# reLoaD_Spinner.net
KiCad netlist of a schematic drawn in EAGLE
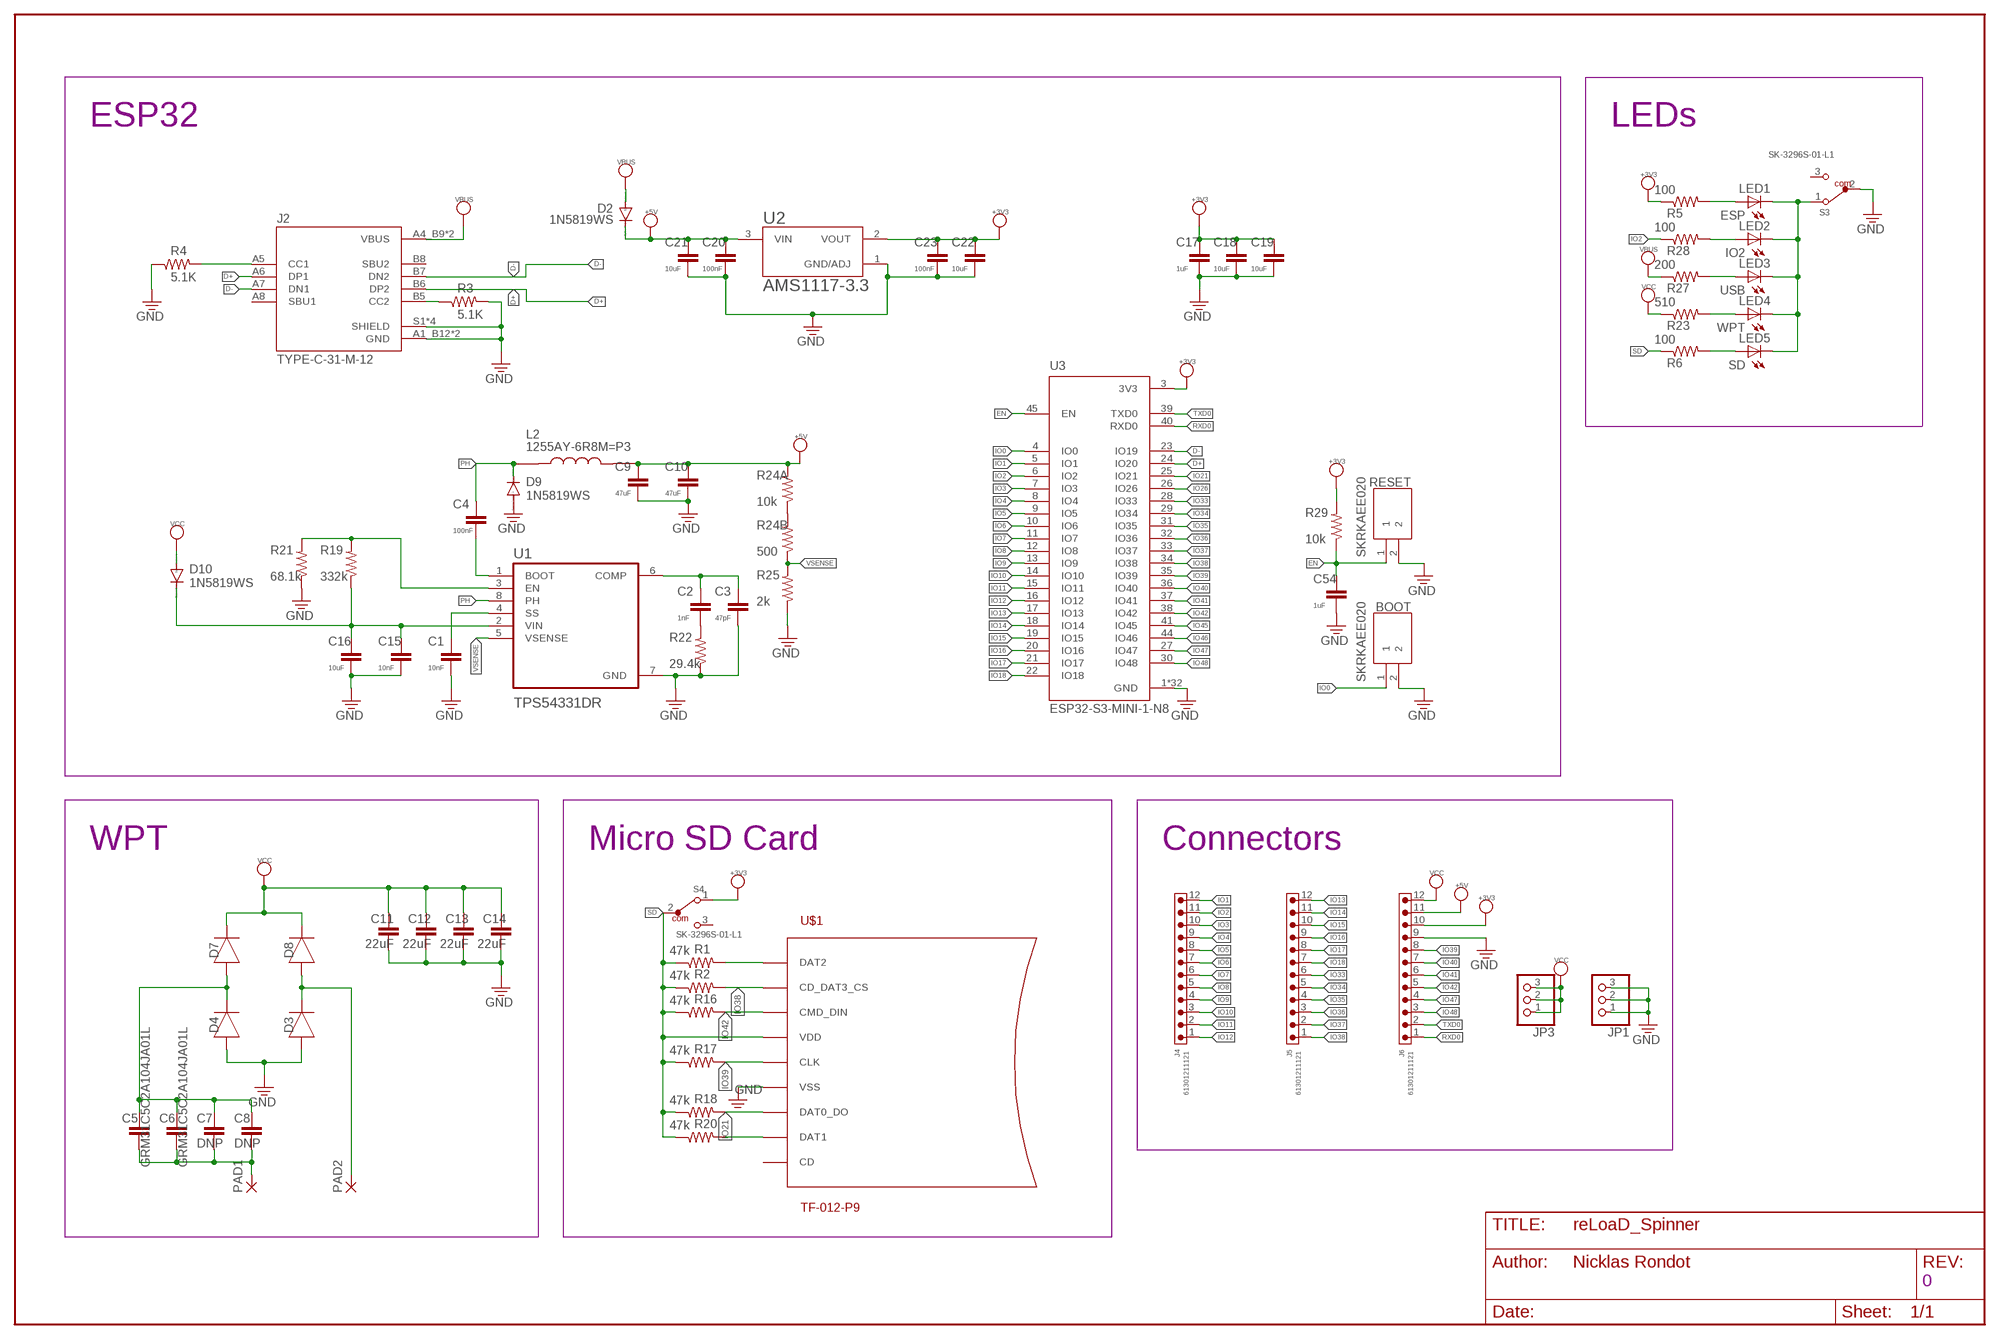
[diagram p0: schematic, sheet 1]

(export (version "E")
  (design (tool "Eeschema 10.0.6"))
  (components
    (comp (ref "BOOT")
      (value "SKRKAEE020")
      (footprint "eagle-import:SKRKAEE020")
      (fields (field (name "MOUSER_PART_NUMBER") "688-SKRKAEE020"))
      (libsource (lib "eagle-import") (part "SKRKAEE020"))
    )
    (comp (ref "C1")
      (value "10nF")
      (footprint "eagle-import:C0603K")
      (libsource (lib "eagle-import") (part "resistor_348_C-EUC0603K"))
    )
    (comp (ref "C2")
      (value "1nF")
      (footprint "eagle-import:C0603K")
      (libsource (lib "eagle-import") (part "resistor_348_C-EUC0603K"))
    )
    (comp (ref "C3")
      (value "47pF")
      (footprint "eagle-import:C0603K")
      (libsource (lib "eagle-import") (part "resistor_348_C-EUC0603K"))
    )
    (comp (ref "C4")
      (value "100nF")
      (footprint "eagle-import:C0603K")
      (libsource (lib "eagle-import") (part "resistor_348_C-EUC0603K"))
    )
    (comp (ref "C5")
      (value "GRM31C5C2A104JA01L")
      (footprint "eagle-import:C1206K")
      (libsource (lib "eagle-import") (part "C-EUC1206K"))
    )
    (comp (ref "C6")
      (value "GRM31C5C2A104JA01L")
      (footprint "eagle-import:C1206K")
      (libsource (lib "eagle-import") (part "C-EUC1206K"))
    )
    (comp (ref "C7")
      (value "DNP")
      (footprint "eagle-import:C1206K")
      (libsource (lib "eagle-import") (part "C-EUC1206K"))
    )
    (comp (ref "C8")
      (value "DNP")
      (footprint "eagle-import:C1206K")
      (libsource (lib "eagle-import") (part "C-EUC1206K"))
    )
    (comp (ref "C9")
      (value "47uF")
      (footprint "eagle-import:C0603K")
      (libsource (lib "eagle-import") (part "resistor_348_C-EUC0603K"))
    )
    (comp (ref "C10")
      (value "47uF")
      (footprint "eagle-import:C0603K")
      (libsource (lib "eagle-import") (part "resistor_348_C-EUC0603K"))
    )
    (comp (ref "C11")
      (value "22uF")
      (footprint "eagle-import:C0805K")
      (libsource (lib "eagle-import") (part "C-EUC0805K"))
    )
    (comp (ref "C12")
      (value "22uF")
      (footprint "eagle-import:C0805K")
      (libsource (lib "eagle-import") (part "C-EUC0805K"))
    )
    (comp (ref "C13")
      (value "22uF")
      (footprint "eagle-import:C0805K")
      (libsource (lib "eagle-import") (part "C-EUC0805K"))
    )
    (comp (ref "C14")
      (value "22uF")
      (footprint "eagle-import:C0805K")
      (libsource (lib "eagle-import") (part "C-EUC0805K"))
    )
    (comp (ref "C15")
      (value "10nF")
      (footprint "eagle-import:C0603K")
      (libsource (lib "eagle-import") (part "resistor_348_C-EUC0603K"))
    )
    (comp (ref "C16")
      (value "10uF")
      (footprint "eagle-import:C0603K")
      (libsource (lib "eagle-import") (part "resistor_348_C-EUC0603K"))
    )
    (comp (ref "C17")
      (value "1uF")
      (footprint "eagle-import:C0603K")
      (libsource (lib "eagle-import") (part "resistor_348_C-EUC0603K"))
    )
    (comp (ref "C18")
      (value "10uF")
      (footprint "eagle-import:C0603K")
      (libsource (lib "eagle-import") (part "resistor_348_C-EUC0603K"))
    )
    (comp (ref "C19")
      (value "10uF")
      (footprint "eagle-import:C0603K")
      (libsource (lib "eagle-import") (part "resistor_348_C-EUC0603K"))
    )
    (comp (ref "C20")
      (value "100nF")
      (footprint "eagle-import:C0603K")
      (libsource (lib "eagle-import") (part "resistor_348_C-EUC0603K"))
    )
    (comp (ref "C21")
      (value "10uF")
      (footprint "eagle-import:C0603K")
      (libsource (lib "eagle-import") (part "resistor_348_C-EUC0603K"))
    )
    (comp (ref "C22")
      (value "10uF")
      (footprint "eagle-import:C0603K")
      (libsource (lib "eagle-import") (part "resistor_348_C-EUC0603K"))
    )
    (comp (ref "C23")
      (value "100nF")
      (footprint "eagle-import:C0603K")
      (libsource (lib "eagle-import") (part "resistor_348_C-EUC0603K"))
    )
    (comp (ref "C54")
      (value "1uF")
      (footprint "eagle-import:C0603K")
      (libsource (lib "eagle-import") (part "resistor_348_C-EUC0603K"))
    )
    (comp (ref "D2")
      (value "1N5819WS")
      (footprint "eagle-import:SOD323-W")
      (libsource (lib "eagle-import") (part "DIODE-SOD323-W"))
    )
    (comp (ref "D3")
      (value "DIODE")
      (footprint "eagle-import:DIOM5226X290N")
      (libsource (lib "eagle-import") (part "DIODEDO-214AC(SMA)"))
    )
    (comp (ref "D4")
      (value "DIODE")
      (footprint "eagle-import:DIOM5226X290N")
      (libsource (lib "eagle-import") (part "DIODEDO-214AC(SMA)"))
    )
    (comp (ref "D7")
      (value "DIODE")
      (footprint "eagle-import:DIOM5226X290N")
      (libsource (lib "eagle-import") (part "DIODEDO-214AC(SMA)"))
    )
    (comp (ref "D8")
      (value "DIODE")
      (footprint "eagle-import:DIOM5226X290N")
      (libsource (lib "eagle-import") (part "DIODEDO-214AC(SMA)"))
    )
    (comp (ref "D9")
      (value "1N5819WS")
      (footprint "eagle-import:SOD323-W")
      (libsource (lib "eagle-import") (part "DIODE-SOD323-W"))
    )
    (comp (ref "D10")
      (value "1N5819WS")
      (footprint "eagle-import:SOD323-W")
      (libsource (lib "eagle-import") (part "DIODE-SOD323-W"))
    )
    (comp (ref "J2")
      (value "TYPE-C-31-M-12")
      (footprint "eagle-import:HRO_TYPE-C-31-M-12")
      (fields (field (name "MF") "HRO Electronics Co., Ltd."))
      (libsource (lib "eagle-import") (part "TYPE-C-31-M-12"))
    )
    (comp (ref "J4")
      (value "61301211121")
      (footprint "eagle-import:61301211121")
      (libsource (lib "eagle-import") (part "6130XX11121_61301211121"))
    )
    (comp (ref "J5")
      (value "61301211121")
      (footprint "eagle-import:61301211121")
      (libsource (lib "eagle-import") (part "6130XX11121_61301211121"))
    )
    (comp (ref "J6")
      (value "61301211121")
      (footprint "eagle-import:61301211121")
      (libsource (lib "eagle-import") (part "6130XX11121_61301211121"))
    )
    (comp (ref "JP1")
      (value "PINHD-1X3")
      (footprint "eagle-import:1X03")
      (libsource (lib "eagle-import") (part "PINHD-1X3"))
    )
    (comp (ref "JP3")
      (value "PINHD-1X3")
      (footprint "eagle-import:1X03")
      (libsource (lib "eagle-import") (part "PINHD-1X3"))
    )
    (comp (ref "L2")
      (value "1255AY-6R8M=P3")
      (footprint "eagle-import:IND_1255AY-6R8M=P3")
      (fields (field (name "MF") "Murata Electronics"))
      (libsource (lib "eagle-import") (part "1255AY-6R8M=P3"))
    )
    (comp (ref "LED1")
      (value "ESP")
      (footprint "eagle-import:CHIPLED_0805")
      (libsource (lib "eagle-import") (part "LEDCHIPLED_0805"))
    )
    (comp (ref "LED2")
      (value "IO2")
      (footprint "eagle-import:CHIPLED_0805")
      (libsource (lib "eagle-import") (part "LEDCHIPLED_0805"))
    )
    (comp (ref "LED3")
      (value "USB")
      (footprint "eagle-import:CHIPLED_0805")
      (libsource (lib "eagle-import") (part "LEDCHIPLED_0805"))
    )
    (comp (ref "LED4")
      (value "WPT")
      (footprint "eagle-import:CHIPLED_0805")
      (libsource (lib "eagle-import") (part "LEDCHIPLED_0805"))
    )
    (comp (ref "LED5")
      (value "SD")
      (footprint "eagle-import:CHIPLED_0805")
      (libsource (lib "eagle-import") (part "LEDCHIPLED_0805"))
    )
    (comp (ref "PAD1")
      (value "3,81/1,4")
      (footprint "eagle-import:3,81_1,4")
      (libsource (lib "eagle-import") (part "3,81/1,4"))
    )
    (comp (ref "PAD2")
      (value "3,81/1,4")
      (footprint "eagle-import:3,81_1,4")
      (libsource (lib "eagle-import") (part "3,81/1,4"))
    )
    (comp (ref "R1")
      (value "47k")
      (footprint "eagle-import:R0603")
      (libsource (lib "eagle-import") (part "R-US_R0603"))
    )
    (comp (ref "R2")
      (value "47k")
      (footprint "eagle-import:R0603")
      (libsource (lib "eagle-import") (part "R-US_R0603"))
    )
    (comp (ref "R3")
      (value "5.1K")
      (footprint "eagle-import:R0603")
      (libsource (lib "eagle-import") (part "R-US_R0603"))
    )
    (comp (ref "R4")
      (value "5.1K")
      (footprint "eagle-import:R0603")
      (libsource (lib "eagle-import") (part "R-US_R0603"))
    )
    (comp (ref "R5")
      (value "100")
      (footprint "eagle-import:R0603")
      (libsource (lib "eagle-import") (part "R-US_R0603"))
    )
    (comp (ref "R6")
      (value "100")
      (footprint "eagle-import:R0603")
      (libsource (lib "eagle-import") (part "R-US_R0603"))
    )
    (comp (ref "R16")
      (value "47k")
      (footprint "eagle-import:R0603")
      (libsource (lib "eagle-import") (part "R-US_R0603"))
    )
    (comp (ref "R17")
      (value "47k")
      (footprint "eagle-import:R0603")
      (libsource (lib "eagle-import") (part "R-US_R0603"))
    )
    (comp (ref "R18")
      (value "47k")
      (footprint "eagle-import:R0603")
      (libsource (lib "eagle-import") (part "R-US_R0603"))
    )
    (comp (ref "R19")
      (value "332k")
      (footprint "eagle-import:R0603")
      (libsource (lib "eagle-import") (part "R-US_R0603"))
    )
    (comp (ref "R20")
      (value "47k")
      (footprint "eagle-import:R0603")
      (libsource (lib "eagle-import") (part "R-US_R0603"))
    )
    (comp (ref "R21")
      (value "68.1k")
      (footprint "eagle-import:R0603")
      (libsource (lib "eagle-import") (part "R-US_R0603"))
    )
    (comp (ref "R22")
      (value "29.4k")
      (footprint "eagle-import:R0603")
      (libsource (lib "eagle-import") (part "R-US_R0603"))
    )
    (comp (ref "R23")
      (value "510")
      (footprint "eagle-import:R0603")
      (libsource (lib "eagle-import") (part "R-US_R0603"))
    )
    (comp (ref "R24A")
      (value "10k")
      (footprint "eagle-import:R0603")
      (libsource (lib "eagle-import") (part "R-US_R0603"))
    )
    (comp (ref "R24B")
      (value "500")
      (footprint "eagle-import:R0603")
      (libsource (lib "eagle-import") (part "R-US_R0603"))
    )
    (comp (ref "R25")
      (value "2k")
      (footprint "eagle-import:R0603")
      (libsource (lib "eagle-import") (part "R-US_R0603"))
    )
    (comp (ref "R27")
      (value "200")
      (footprint "eagle-import:R0603")
      (libsource (lib "eagle-import") (part "R-US_R0603"))
    )
    (comp (ref "R28")
      (value "100")
      (footprint "eagle-import:R0603")
      (libsource (lib "eagle-import") (part "R-US_R0603"))
    )
    (comp (ref "R29")
      (value "10k")
      (footprint "eagle-import:R0603")
      (libsource (lib "eagle-import") (part "R-US_R0603"))
    )
    (comp (ref "RESET")
      (value "SKRKAEE020")
      (footprint "eagle-import:SKRKAEE020")
      (fields (field (name "MOUSER_PART_NUMBER") "688-SKRKAEE020"))
      (libsource (lib "eagle-import") (part "SKRKAEE020"))
    )
    (comp (ref "S3")
      (value "SK-3296S-01-L1")
      (footprint "eagle-import:450404015514")
      (libsource (lib "eagle-import") (part "450404015514"))
    )
    (comp (ref "S4")
      (value "SK-3296S-01-L1")
      (footprint "eagle-import:450404015514")
      (libsource (lib "eagle-import") (part "450404015514"))
    )
    (comp (ref "U$1")
      (value "TF-012-P9")
      (footprint "eagle-import:MICROSD-PUSH-OUT")
      (libsource (lib "eagle-import") (part "TF-012-P9"))
    )
    (comp (ref "U1")
      (value "TPS54331DR")
      (footprint "eagle-import:SOIC127P599X175-8N")
      (fields (field (name "MF") "Texas Instruments"))
      (libsource (lib "eagle-import") (part "TPS54331DR"))
    )
    (comp (ref "U2")
      (value "AMS1117-3.3")
      (footprint "eagle-import:SOT229P700X180-4N")
      (fields (field (name "MF") "Advanced Monolithic Systems"))
      (libsource (lib "eagle-import") (part "AMS1117-3.3"))
    )
    (comp (ref "U3")
      (value "ESP32-S3-MINI-1-N8")
      (footprint "eagle-import:XCVR_ESP32-S3-MINI-1-N8")
      (fields (field (name "MF") "Espressif Systems"))
      (libsource (lib "eagle-import") (part "ESP32-S3-MINI-1-N8"))
    )
  )
  (nets
    (net (code "1") (name "+3V3") (class "Default")
      (node (ref "C17") (pin "1") (pinfunction "1_1") (pintype "passive"))
      (node (ref "C18") (pin "1") (pinfunction "1_1") (pintype "passive"))
      (node (ref "C19") (pin "1") (pinfunction "1_1") (pintype "passive"))
      (node (ref "C22") (pin "1") (pinfunction "1_1") (pintype "passive"))
      (node (ref "C23") (pin "1") (pinfunction "1_1") (pintype "passive"))
      (node (ref "J6") (pin "10") (pinfunction "10_10") (pintype "passive"))
      (node (ref "R29") (pin "2") (pinfunction "2_2") (pintype "passive"))
      (node (ref "R5") (pin "1") (pinfunction "1_1") (pintype "passive"))
      (node (ref "S4") (pin "1") (pinfunction "1_1") (pintype "passive"))
      (node (ref "U2") (pin "2") (pinfunction "VOUT_2") (pintype "output"))
      (node (ref "U3") (pin "3") (pinfunction "3V3_3") (pintype "power_in"))
    )
    (net (code "2") (name "+5V") (class "Default")
      (node (ref "C10") (pin "1") (pinfunction "1_1") (pintype "passive"))
      (node (ref "C20") (pin "1") (pinfunction "1_1") (pintype "passive"))
      (node (ref "C21") (pin "1") (pinfunction "1_1") (pintype "passive"))
      (node (ref "C9") (pin "1") (pinfunction "1_1") (pintype "passive"))
      (node (ref "D2") (pin "C") (pinfunction "C_C") (pintype "passive"))
      (node (ref "J6") (pin "11") (pinfunction "11_11") (pintype "passive"))
      (node (ref "L2") (pin "2") (pinfunction "2_2") (pintype "passive"))
      (node (ref "R24A") (pin "2") (pinfunction "2_2") (pintype "passive"))
      (node (ref "U2") (pin "3") (pinfunction "VIN_3") (pintype "input"))
    )
    (net (code "3") (name "D+") (class "Default")
      (node (ref "J2") (pin "A6") (pinfunction "DP1_A6") (pintype "bidirectional"))
      (node (ref "J2") (pin "B6") (pinfunction "DP2_B6") (pintype "bidirectional"))
      (node (ref "U3") (pin "24") (pinfunction "IO20_24") (pintype "bidirectional"))
    )
    (net (code "4") (name "D-") (class "Default")
      (node (ref "J2") (pin "A7") (pinfunction "DN1_A7") (pintype "bidirectional"))
      (node (ref "J2") (pin "B7") (pinfunction "DN2_B7") (pintype "bidirectional"))
      (node (ref "U3") (pin "23") (pinfunction "IO19_23") (pintype "bidirectional"))
    )
    (net (code "5") (name "EN") (class "Default")
      (node (ref "C54") (pin "1") (pinfunction "1_1") (pintype "passive"))
      (node (ref "R29") (pin "1") (pinfunction "1_1") (pintype "passive"))
      (node (ref "RESET") (pin "1") (pinfunction "1_1") (pintype "bidirectional"))
      (node (ref "U3") (pin "45") (pinfunction "EN_45") (pintype "input"))
    )
    (net (code "6") (name "GND") (class "Default")
      (node (ref "BOOT") (pin "2") (pinfunction "2_2") (pintype "bidirectional"))
      (node (ref "C1") (pin "2") (pinfunction "2_2") (pintype "passive"))
      (node (ref "C10") (pin "2") (pinfunction "2_2") (pintype "passive"))
      (node (ref "C11") (pin "1") (pinfunction "1_1") (pintype "passive"))
      (node (ref "C12") (pin "1") (pinfunction "1_1") (pintype "passive"))
      (node (ref "C13") (pin "1") (pinfunction "1_1") (pintype "passive"))
      (node (ref "C14") (pin "1") (pinfunction "1_1") (pintype "passive"))
      (node (ref "C15") (pin "2") (pinfunction "2_2") (pintype "passive"))
      (node (ref "C16") (pin "2") (pinfunction "2_2") (pintype "passive"))
      (node (ref "C17") (pin "2") (pinfunction "2_2") (pintype "passive"))
      (node (ref "C18") (pin "2") (pinfunction "2_2") (pintype "passive"))
      (node (ref "C19") (pin "2") (pinfunction "2_2") (pintype "passive"))
      (node (ref "C20") (pin "2") (pinfunction "2_2") (pintype "passive"))
      (node (ref "C21") (pin "2") (pinfunction "2_2") (pintype "passive"))
      (node (ref "C22") (pin "2") (pinfunction "2_2") (pintype "passive"))
      (node (ref "C23") (pin "2") (pinfunction "2_2") (pintype "passive"))
      (node (ref "C3") (pin "2") (pinfunction "2_2") (pintype "passive"))
      (node (ref "C54") (pin "2") (pinfunction "2_2") (pintype "passive"))
      (node (ref "C9") (pin "2") (pinfunction "2_2") (pintype "passive"))
      (node (ref "D3") (pin "2") (pinfunction "A_2") (pintype "passive"))
      (node (ref "D4") (pin "2") (pinfunction "A_2") (pintype "passive"))
      (node (ref "D9") (pin "A") (pinfunction "A_A") (pintype "passive"))
      (node (ref "J2") (pin "A1_B12") (pinfunction "GND_A1_B12") (pintype "power_in"))
      (node (ref "J2") (pin "B1_A12") (pinfunction "GND_B1_A12") (pintype "power_in"))
      (node (ref "J2") (pin "S1") (pinfunction "SHIELD_S1") (pintype "passive"))
      (node (ref "J2") (pin "S2") (pinfunction "SHIELD_S2") (pintype "passive"))
      (node (ref "J2") (pin "S3") (pinfunction "SHIELD_S3") (pintype "passive"))
      (node (ref "J2") (pin "S4") (pinfunction "SHIELD_S4") (pintype "passive"))
      (node (ref "J6") (pin "9") (pinfunction "9_9") (pintype "passive"))
      (node (ref "JP1") (pin "1") (pinfunction "1_1") (pintype "passive"))
      (node (ref "JP1") (pin "2") (pinfunction "2_2") (pintype "passive"))
      (node (ref "JP1") (pin "3") (pinfunction "3_3") (pintype "passive"))
      (node (ref "R21") (pin "1") (pinfunction "1_1") (pintype "passive"))
      (node (ref "R22") (pin "1") (pinfunction "1_1") (pintype "passive"))
      (node (ref "R25") (pin "1") (pinfunction "1_1") (pintype "passive"))
      (node (ref "R3") (pin "2") (pinfunction "2_2") (pintype "passive"))
      (node (ref "R4") (pin "1") (pinfunction "1_1") (pintype "passive"))
      (node (ref "RESET") (pin "2") (pinfunction "2_2") (pintype "bidirectional"))
      (node (ref "S3") (pin "2") (pinfunction "2_2") (pintype "passive"))
      (node (ref "U$1") (pin "6") (pinfunction "VSS_6") (pintype "bidirectional"))
      (node (ref "U$1") (pin "G1") (pinfunction "VSS_G1") (pintype "bidirectional"))
      (node (ref "U$1") (pin "G2") (pinfunction "VSS_G2") (pintype "bidirectional"))
      (node (ref "U$1") (pin "G3") (pinfunction "VSS_G3") (pintype "bidirectional"))
      (node (ref "U$1") (pin "G4") (pinfunction "VSS_G4") (pintype "bidirectional"))
      (node (ref "U1") (pin "7") (pinfunction "GND_7") (pintype "power_in"))
      (node (ref "U2") (pin "1") (pinfunction "GND/ADJ_1") (pintype "power_in"))
      (node (ref "U3") (pin "1") (pinfunction "GND_1") (pintype "power_in"))
      (node (ref "U3") (pin "2") (pinfunction "GND_2") (pintype "power_in"))
      (node (ref "U3") (pin "42") (pinfunction "GND_42") (pintype "power_in"))
      (node (ref "U3") (pin "43") (pinfunction "GND_43") (pintype "power_in"))
      (node (ref "U3") (pin "46") (pinfunction "GND_46") (pintype "power_in"))
      (node (ref "U3") (pin "47") (pinfunction "GND_47") (pintype "power_in"))
      (node (ref "U3") (pin "48") (pinfunction "GND_48") (pintype "power_in"))
      (node (ref "U3") (pin "49") (pinfunction "GND_49") (pintype "power_in"))
      (node (ref "U3") (pin "50") (pinfunction "GND_50") (pintype "power_in"))
      (node (ref "U3") (pin "51") (pinfunction "GND_51") (pintype "power_in"))
      (node (ref "U3") (pin "52") (pinfunction "GND_52") (pintype "power_in"))
      (node (ref "U3") (pin "53") (pinfunction "GND_53") (pintype "power_in"))
      (node (ref "U3") (pin "54") (pinfunction "GND_54") (pintype "power_in"))
      (node (ref "U3") (pin "55") (pinfunction "GND_55") (pintype "power_in"))
      (node (ref "U3") (pin "56") (pinfunction "GND_56") (pintype "power_in"))
      (node (ref "U3") (pin "57") (pinfunction "GND_57") (pintype "power_in"))
      (node (ref "U3") (pin "58") (pinfunction "GND_58") (pintype "power_in"))
      (node (ref "U3") (pin "59") (pinfunction "GND_59") (pintype "power_in"))
      (node (ref "U3") (pin "60") (pinfunction "GND_60") (pintype "power_in"))
      (node (ref "U3") (pin "61") (pinfunction "GND_61") (pintype "power_in"))
      (node (ref "U3") (pin "61_1") (pinfunction "GND_61_1") (pintype "power_in"))
      (node (ref "U3") (pin "61_2") (pinfunction "GND_61_2") (pintype "power_in"))
      (node (ref "U3") (pin "61_3") (pinfunction "GND_61_3") (pintype "power_in"))
      (node (ref "U3") (pin "61_4") (pinfunction "GND_61_4") (pintype "power_in"))
      (node (ref "U3") (pin "61_5") (pinfunction "GND_61_5") (pintype "power_in"))
      (node (ref "U3") (pin "61_6") (pinfunction "GND_61_6") (pintype "power_in"))
      (node (ref "U3") (pin "61_7") (pinfunction "GND_61_7") (pintype "power_in"))
      (node (ref "U3") (pin "61_8") (pinfunction "GND_61_8") (pintype "power_in"))
      (node (ref "U3") (pin "62") (pinfunction "GND_62") (pintype "power_in"))
      (node (ref "U3") (pin "63") (pinfunction "GND_63") (pintype "power_in"))
      (node (ref "U3") (pin "64") (pinfunction "GND_64") (pintype "power_in"))
      (node (ref "U3") (pin "65") (pinfunction "GND_65") (pintype "power_in"))
    )
    (net (code "7") (name "IO0") (class "Default")
      (node (ref "BOOT") (pin "1") (pinfunction "1_1") (pintype "bidirectional"))
      (node (ref "U3") (pin "4") (pinfunction "IO0_4") (pintype "bidirectional"))
    )
    (net (code "8") (name "IO1") (class "Default")
      (node (ref "J4") (pin "12") (pinfunction "12_12") (pintype "passive"))
      (node (ref "U3") (pin "5") (pinfunction "IO1_5") (pintype "bidirectional"))
    )
    (net (code "9") (name "IO2") (class "Default")
      (node (ref "J4") (pin "11") (pinfunction "11_11") (pintype "passive"))
      (node (ref "R28") (pin "1") (pinfunction "1_1") (pintype "passive"))
      (node (ref "U3") (pin "6") (pinfunction "IO2_6") (pintype "bidirectional"))
    )
    (net (code "10") (name "IO3") (class "Default")
      (node (ref "J4") (pin "10") (pinfunction "10_10") (pintype "passive"))
      (node (ref "U3") (pin "7") (pinfunction "IO3_7") (pintype "bidirectional"))
    )
    (net (code "11") (name "IO4") (class "Default")
      (node (ref "J4") (pin "9") (pinfunction "9_9") (pintype "passive"))
      (node (ref "U3") (pin "8") (pinfunction "IO4_8") (pintype "bidirectional"))
    )
    (net (code "12") (name "IO5") (class "Default")
      (node (ref "J4") (pin "8") (pinfunction "8_8") (pintype "passive"))
      (node (ref "U3") (pin "9") (pinfunction "IO5_9") (pintype "bidirectional"))
    )
    (net (code "13") (name "IO6") (class "Default")
      (node (ref "J4") (pin "7") (pinfunction "7_7") (pintype "passive"))
      (node (ref "U3") (pin "10") (pinfunction "IO6_10") (pintype "bidirectional"))
    )
    (net (code "14") (name "IO7") (class "Default")
      (node (ref "J4") (pin "6") (pinfunction "6_6") (pintype "passive"))
      (node (ref "U3") (pin "11") (pinfunction "IO7_11") (pintype "bidirectional"))
    )
    (net (code "15") (name "IO8") (class "Default")
      (node (ref "J4") (pin "5") (pinfunction "5_5") (pintype "passive"))
      (node (ref "U3") (pin "12") (pinfunction "IO8_12") (pintype "bidirectional"))
    )
    (net (code "16") (name "IO9") (class "Default")
      (node (ref "J4") (pin "4") (pinfunction "4_4") (pintype "passive"))
      (node (ref "U3") (pin "13") (pinfunction "IO9_13") (pintype "bidirectional"))
    )
    (net (code "17") (name "IO10") (class "Default")
      (node (ref "J4") (pin "3") (pinfunction "3_3") (pintype "passive"))
      (node (ref "U3") (pin "14") (pinfunction "IO10_14") (pintype "bidirectional"))
    )
    (net (code "18") (name "IO11") (class "Default")
      (node (ref "J4") (pin "2") (pinfunction "2_2") (pintype "passive"))
      (node (ref "U3") (pin "15") (pinfunction "IO11_15") (pintype "bidirectional"))
    )
    (net (code "19") (name "IO12") (class "Default")
      (node (ref "J4") (pin "1") (pinfunction "1_1") (pintype "passive"))
      (node (ref "U3") (pin "16") (pinfunction "IO12_16") (pintype "bidirectional"))
    )
    (net (code "20") (name "IO13") (class "Default")
      (node (ref "J5") (pin "12") (pinfunction "12_12") (pintype "passive"))
      (node (ref "U3") (pin "17") (pinfunction "IO13_17") (pintype "bidirectional"))
    )
    (net (code "21") (name "IO14") (class "Default")
      (node (ref "J5") (pin "11") (pinfunction "11_11") (pintype "passive"))
      (node (ref "U3") (pin "18") (pinfunction "IO14_18") (pintype "bidirectional"))
    )
    (net (code "22") (name "IO15") (class "Default")
      (node (ref "J5") (pin "10") (pinfunction "10_10") (pintype "passive"))
      (node (ref "U3") (pin "19") (pinfunction "IO15_19") (pintype "bidirectional"))
    )
    (net (code "23") (name "IO16") (class "Default")
      (node (ref "J5") (pin "9") (pinfunction "9_9") (pintype "passive"))
      (node (ref "U3") (pin "20") (pinfunction "IO16_20") (pintype "bidirectional"))
    )
    (net (code "24") (name "IO17") (class "Default")
      (node (ref "J5") (pin "8") (pinfunction "8_8") (pintype "passive"))
      (node (ref "U3") (pin "21") (pinfunction "IO17_21") (pintype "bidirectional"))
    )
    (net (code "25") (name "IO18") (class "Default")
      (node (ref "J5") (pin "7") (pinfunction "7_7") (pintype "passive"))
      (node (ref "U3") (pin "22") (pinfunction "IO18_22") (pintype "bidirectional"))
    )
    (net (code "26") (name "IO21") (class "Default")
      (node (ref "R18") (pin "2") (pinfunction "2_2") (pintype "passive"))
      (node (ref "U$1") (pin "7") (pinfunction "DAT0_DO_7") (pintype "bidirectional"))
      (node (ref "U3") (pin "25") (pinfunction "IO21_25") (pintype "bidirectional"))
    )
    (net (code "27") (name "IO26") (class "Default")
      (node (ref "U3") (pin "26") (pinfunction "IO26_26") (pintype "bidirectional"))
    )
    (net (code "28") (name "IO33") (class "Default")
      (node (ref "J5") (pin "6") (pinfunction "6_6") (pintype "passive"))
      (node (ref "U3") (pin "28") (pinfunction "IO33_28") (pintype "bidirectional"))
    )
    (net (code "29") (name "IO34") (class "Default")
      (node (ref "J5") (pin "5") (pinfunction "5_5") (pintype "passive"))
      (node (ref "U3") (pin "29") (pinfunction "IO34_29") (pintype "bidirectional"))
    )
    (net (code "30") (name "IO35") (class "Default")
      (node (ref "J5") (pin "4") (pinfunction "4_4") (pintype "passive"))
      (node (ref "U3") (pin "31") (pinfunction "IO35_31") (pintype "bidirectional"))
    )
    (net (code "31") (name "IO36") (class "Default")
      (node (ref "J5") (pin "3") (pinfunction "3_3") (pintype "passive"))
      (node (ref "U3") (pin "32") (pinfunction "IO36_32") (pintype "bidirectional"))
    )
    (net (code "32") (name "IO37") (class "Default")
      (node (ref "J5") (pin "2") (pinfunction "2_2") (pintype "passive"))
      (node (ref "U3") (pin "33") (pinfunction "IO37_33") (pintype "bidirectional"))
    )
    (net (code "33") (name "IO38") (class "Default")
      (node (ref "J5") (pin "1") (pinfunction "1_1") (pintype "passive"))
      (node (ref "R2") (pin "2") (pinfunction "2_2") (pintype "passive"))
      (node (ref "U$1") (pin "2") (pinfunction "CD_DAT3_CS_2") (pintype "bidirectional"))
      (node (ref "U3") (pin "34") (pinfunction "IO38_34") (pintype "bidirectional"))
    )
    (net (code "34") (name "IO39") (class "Default")
      (node (ref "J6") (pin "8") (pinfunction "8_8") (pintype "passive"))
      (node (ref "R17") (pin "2") (pinfunction "2_2") (pintype "passive"))
      (node (ref "U$1") (pin "5") (pinfunction "CLK_5") (pintype "bidirectional"))
      (node (ref "U3") (pin "35") (pinfunction "IO39_35") (pintype "bidirectional"))
    )
    (net (code "35") (name "IO40") (class "Default")
      (node (ref "J6") (pin "7") (pinfunction "7_7") (pintype "passive"))
      (node (ref "U3") (pin "36") (pinfunction "IO40_36") (pintype "bidirectional"))
    )
    (net (code "36") (name "IO41") (class "Default")
      (node (ref "J6") (pin "6") (pinfunction "6_6") (pintype "passive"))
      (node (ref "U3") (pin "37") (pinfunction "IO41_37") (pintype "bidirectional"))
    )
    (net (code "37") (name "IO42") (class "Default")
      (node (ref "J6") (pin "5") (pinfunction "5_5") (pintype "passive"))
      (node (ref "R16") (pin "2") (pinfunction "2_2") (pintype "passive"))
      (node (ref "U$1") (pin "3") (pinfunction "CMD_DIN_3") (pintype "bidirectional"))
      (node (ref "U3") (pin "38") (pinfunction "IO42_38") (pintype "bidirectional"))
    )
    (net (code "38") (name "IO45") (class "Default")
      (node (ref "U3") (pin "41") (pinfunction "IO45_41") (pintype "bidirectional"))
    )
    (net (code "39") (name "IO46") (class "Default")
      (node (ref "U3") (pin "44") (pinfunction "IO46_44") (pintype "bidirectional"))
    )
    (net (code "40") (name "IO47") (class "Default")
      (node (ref "J6") (pin "4") (pinfunction "4_4") (pintype "passive"))
      (node (ref "U3") (pin "27") (pinfunction "IO47_27") (pintype "bidirectional"))
    )
    (net (code "41") (name "IO48") (class "Default")
      (node (ref "J6") (pin "3") (pinfunction "3_3") (pintype "passive"))
      (node (ref "U3") (pin "30") (pinfunction "IO48_30") (pintype "bidirectional"))
    )
    (net (code "42") (name "Net-(C2-Pad2)") (class "Default")
      (node (ref "C2") (pin "2") (pinfunction "2_2") (pintype "passive"))
      (node (ref "R22") (pin "2") (pinfunction "2_2") (pintype "passive"))
    )
    (net (code "43") (name "Net-(D3-C)") (class "Default")
      (node (ref "D3") (pin "1") (pinfunction "C_1") (pintype "passive"))
      (node (ref "D8") (pin "2") (pinfunction "A_2") (pintype "passive"))
      (node (ref "PAD2") (pin "1") (pinfunction "P_1") (pintype "passive"))
    )
    (net (code "44") (name "Net-(D4-C)") (class "Default")
      (node (ref "C5") (pin "1") (pinfunction "1_1") (pintype "passive"))
      (node (ref "C6") (pin "1") (pinfunction "1_1") (pintype "passive"))
      (node (ref "C7") (pin "1") (pinfunction "1_1") (pintype "passive"))
      (node (ref "C8") (pin "1") (pinfunction "1_1") (pintype "passive"))
      (node (ref "D4") (pin "1") (pinfunction "C_1") (pintype "passive"))
      (node (ref "D7") (pin "2") (pinfunction "A_2") (pintype "passive"))
    )
    (net (code "45") (name "Net-(J2-CC1)") (class "Default")
      (node (ref "J2") (pin "A5") (pinfunction "CC1_A5") (pintype "bidirectional"))
      (node (ref "R4") (pin "2") (pinfunction "2_2") (pintype "passive"))
    )
    (net (code "46") (name "Net-(J2-CC2)") (class "Default")
      (node (ref "J2") (pin "B5") (pinfunction "CC2_B5") (pintype "bidirectional"))
      (node (ref "R3") (pin "1") (pinfunction "1_1") (pintype "passive"))
    )
    (net (code "47") (name "Net-(LED1-PadA)") (class "Default")
      (node (ref "LED1") (pin "A") (pinfunction "A_A") (pintype "passive"))
      (node (ref "R5") (pin "2") (pinfunction "2_2") (pintype "passive"))
    )
    (net (code "48") (name "Net-(LED1-PadC)") (class "Default")
      (node (ref "LED1") (pin "C") (pinfunction "C_C") (pintype "passive"))
      (node (ref "LED2") (pin "C") (pinfunction "C_C") (pintype "passive"))
      (node (ref "LED3") (pin "C") (pinfunction "C_C") (pintype "passive"))
      (node (ref "LED4") (pin "C") (pinfunction "C_C") (pintype "passive"))
      (node (ref "LED5") (pin "C") (pinfunction "C_C") (pintype "passive"))
      (node (ref "S3") (pin "1") (pinfunction "1_1") (pintype "passive"))
    )
    (net (code "49") (name "Net-(LED2-PadA)") (class "Default")
      (node (ref "LED2") (pin "A") (pinfunction "A_A") (pintype "passive"))
      (node (ref "R28") (pin "2") (pinfunction "2_2") (pintype "passive"))
    )
    (net (code "50") (name "Net-(LED3-PadA)") (class "Default")
      (node (ref "LED3") (pin "A") (pinfunction "A_A") (pintype "passive"))
      (node (ref "R27") (pin "2") (pinfunction "2_2") (pintype "passive"))
    )
    (net (code "51") (name "Net-(LED4-PadA)") (class "Default")
      (node (ref "LED4") (pin "A") (pinfunction "A_A") (pintype "passive"))
      (node (ref "R23") (pin "2") (pinfunction "2_2") (pintype "passive"))
    )
    (net (code "52") (name "Net-(LED5-PadA)") (class "Default")
      (node (ref "LED5") (pin "A") (pinfunction "A_A") (pintype "passive"))
      (node (ref "R6") (pin "2") (pinfunction "2_2") (pintype "passive"))
    )
    (net (code "53") (name "Net-(PAD1-P)") (class "Default")
      (node (ref "C5") (pin "2") (pinfunction "2_2") (pintype "passive"))
      (node (ref "C6") (pin "2") (pinfunction "2_2") (pintype "passive"))
      (node (ref "C7") (pin "2") (pinfunction "2_2") (pintype "passive"))
      (node (ref "C8") (pin "2") (pinfunction "2_2") (pintype "passive"))
      (node (ref "PAD1") (pin "1") (pinfunction "P_1") (pintype "passive"))
    )
    (net (code "54") (name "Net-(R24A-Pad1)") (class "Default")
      (node (ref "R24A") (pin "1") (pinfunction "1_1") (pintype "passive"))
      (node (ref "R24B") (pin "2") (pinfunction "2_2") (pintype "passive"))
    )
    (net (code "55") (name "Net-(U$1-DAT1)") (class "Default")
      (node (ref "R20") (pin "2") (pinfunction "2_2") (pintype "passive"))
      (node (ref "U$1") (pin "8") (pinfunction "DAT1_8") (pintype "bidirectional"))
    )
    (net (code "56") (name "Net-(U$1-DAT2)") (class "Default")
      (node (ref "R1") (pin "2") (pinfunction "2_2") (pintype "passive"))
      (node (ref "U$1") (pin "1") (pinfunction "DAT2_1") (pintype "bidirectional"))
    )
    (net (code "57") (name "Net-(U1-BOOT)") (class "Default")
      (node (ref "C4") (pin "2") (pinfunction "2_2") (pintype "passive"))
      (node (ref "U1") (pin "1") (pinfunction "BOOT_1") (pintype "input"))
    )
    (net (code "58") (name "Net-(U1-COMP)") (class "Default")
      (node (ref "C2") (pin "1") (pinfunction "1_1") (pintype "passive"))
      (node (ref "C3") (pin "1") (pinfunction "1_1") (pintype "passive"))
      (node (ref "U1") (pin "6") (pinfunction "COMP_6") (pintype "output"))
    )
    (net (code "59") (name "Net-(U1-EN)") (class "Default")
      (node (ref "R19") (pin "2") (pinfunction "2_2") (pintype "passive"))
      (node (ref "R21") (pin "2") (pinfunction "2_2") (pintype "passive"))
      (node (ref "U1") (pin "3") (pinfunction "EN_3") (pintype "input"))
    )
    (net (code "60") (name "Net-(U1-SS)") (class "Default")
      (node (ref "C1") (pin "1") (pinfunction "1_1") (pintype "passive"))
      (node (ref "U1") (pin "4") (pinfunction "SS_4") (pintype "input"))
    )
    (net (code "61") (name "Net-(U1-VIN)") (class "Default")
      (node (ref "C15") (pin "1") (pinfunction "1_1") (pintype "passive"))
      (node (ref "C16") (pin "1") (pinfunction "1_1") (pintype "passive"))
      (node (ref "D10") (pin "C") (pinfunction "C_C") (pintype "passive"))
      (node (ref "R19") (pin "1") (pinfunction "1_1") (pintype "passive"))
      (node (ref "U1") (pin "2") (pinfunction "VIN_2") (pintype "input"))
    )
    (net (code "62") (name "PH") (class "Default")
      (node (ref "C4") (pin "1") (pinfunction "1_1") (pintype "passive"))
      (node (ref "D9") (pin "C") (pinfunction "C_C") (pintype "passive"))
      (node (ref "L2") (pin "1") (pinfunction "1_1") (pintype "passive"))
      (node (ref "U1") (pin "8") (pinfunction "PH_8") (pintype "input"))
    )
    (net (code "63") (name "RXD0") (class "Default")
      (node (ref "J6") (pin "1") (pinfunction "1_1") (pintype "passive"))
      (node (ref "U3") (pin "40") (pinfunction "RXD0_40") (pintype "bidirectional"))
    )
    (net (code "64") (name "SD") (class "Default")
      (node (ref "R1") (pin "1") (pinfunction "1_1") (pintype "passive"))
      (node (ref "R16") (pin "1") (pinfunction "1_1") (pintype "passive"))
      (node (ref "R17") (pin "1") (pinfunction "1_1") (pintype "passive"))
      (node (ref "R18") (pin "1") (pinfunction "1_1") (pintype "passive"))
      (node (ref "R2") (pin "1") (pinfunction "1_1") (pintype "passive"))
      (node (ref "R20") (pin "1") (pinfunction "1_1") (pintype "passive"))
      (node (ref "R6") (pin "1") (pinfunction "1_1") (pintype "passive"))
      (node (ref "S4") (pin "2") (pinfunction "2_2") (pintype "passive"))
      (node (ref "U$1") (pin "4") (pinfunction "VDD_4") (pintype "bidirectional"))
    )
    (net (code "65") (name "TXD0") (class "Default")
      (node (ref "J6") (pin "2") (pinfunction "2_2") (pintype "passive"))
      (node (ref "U3") (pin "39") (pinfunction "TXD0_39") (pintype "bidirectional"))
    )
    (net (code "66") (name "VBUS") (class "Default")
      (node (ref "D2") (pin "A") (pinfunction "A_A") (pintype "passive"))
      (node (ref "J2") (pin "A4_B9") (pinfunction "VBUS_A4_B9") (pintype "power_in"))
      (node (ref "J2") (pin "B4_A9") (pinfunction "VBUS_B4_A9") (pintype "power_in"))
      (node (ref "R27") (pin "1") (pinfunction "1_1") (pintype "passive"))
    )
    (net (code "67") (name "VCC") (class "Default")
      (node (ref "C11") (pin "2") (pinfunction "2_2") (pintype "passive"))
      (node (ref "C12") (pin "2") (pinfunction "2_2") (pintype "passive"))
      (node (ref "C13") (pin "2") (pinfunction "2_2") (pintype "passive"))
      (node (ref "C14") (pin "2") (pinfunction "2_2") (pintype "passive"))
      (node (ref "D10") (pin "A") (pinfunction "A_A") (pintype "passive"))
      (node (ref "D7") (pin "1") (pinfunction "C_1") (pintype "passive"))
      (node (ref "D8") (pin "1") (pinfunction "C_1") (pintype "passive"))
      (node (ref "J6") (pin "12") (pinfunction "12_12") (pintype "passive"))
      (node (ref "JP3") (pin "1") (pinfunction "1_1") (pintype "passive"))
      (node (ref "JP3") (pin "2") (pinfunction "2_2") (pintype "passive"))
      (node (ref "JP3") (pin "3") (pinfunction "3_3") (pintype "passive"))
      (node (ref "R23") (pin "1") (pinfunction "1_1") (pintype "passive"))
    )
    (net (code "68") (name "VSENSE") (class "Default")
      (node (ref "R24B") (pin "1") (pinfunction "1_1") (pintype "passive"))
      (node (ref "R25") (pin "2") (pinfunction "2_2") (pintype "passive"))
      (node (ref "U1") (pin "5") (pinfunction "VSENSE_5") (pintype "input"))
    )
    (net (code "69") (name "unconnected-(J2-SBU1-PadA8)") (class "Default")
      (node (ref "J2") (pin "A8") (pinfunction "SBU1_A8") (pintype "bidirectional"))
    )
    (net (code "70") (name "unconnected-(J2-SBU2-PadB8)") (class "Default")
      (node (ref "J2") (pin "B8") (pinfunction "SBU2_B8") (pintype "bidirectional"))
    )
    (net (code "71") (name "unconnected-(S3-Pad3)") (class "Default")
      (node (ref "S3") (pin "3") (pinfunction "3_3") (pintype "passive"))
    )
    (net (code "72") (name "unconnected-(S4-Pad3)") (class "Default")
      (node (ref "S4") (pin "3") (pinfunction "3_3") (pintype "passive"))
    )
    (net (code "73") (name "unconnected-(U$1-PadCD)") (class "Default")
      (node (ref "U$1") (pin "CD") (pinfunction "CD_CD") (pintype "bidirectional"))
    )
  )
)
